# BiodataFeather_SymBioWare_001.net
KiCad netlist of a schematic drawn in EAGLE
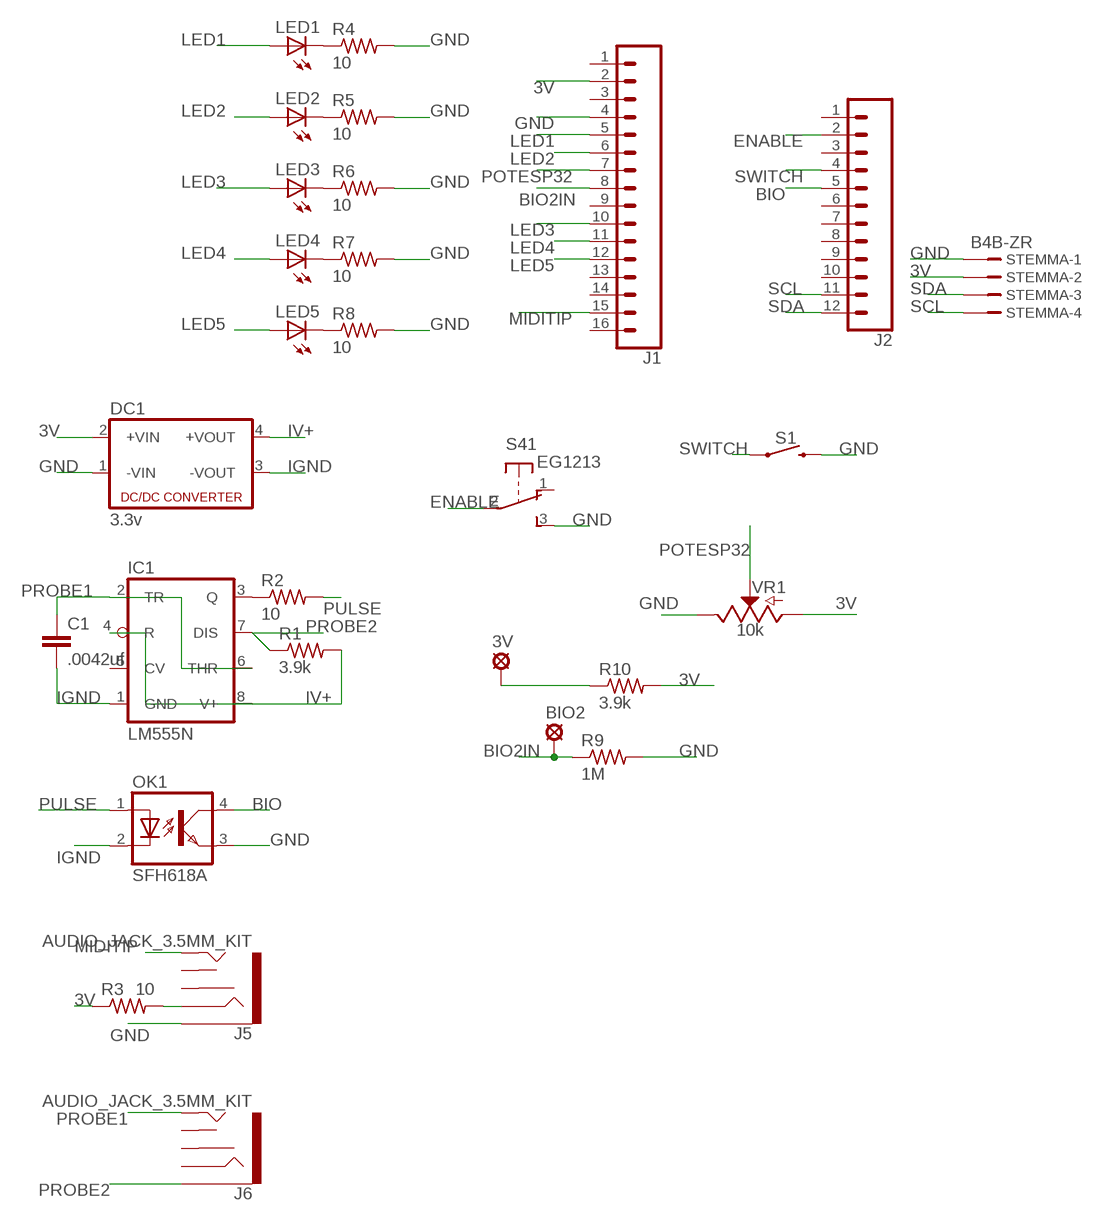
[diagram p0: schematic, sheet 1]

(export (version "E")
  (design (tool "Eeschema 10.0.6"))
  (components
    (comp (ref "3V")
      (value "SE14")
      (footprint "eagle-import:SE14")
      (libsource (lib "eagle-import") (part "SE14"))
    )
    (comp (ref "BIO2")
      (value "SE14")
      (footprint "eagle-import:SE14")
      (libsource (lib "eagle-import") (part "SE14"))
    )
    (comp (ref "C1")
      (value ".0042uf")
      (footprint "eagle-import:C2.5-2")
      (libsource (lib "eagle-import") (part "C2.5/2"))
    )
    (comp (ref "DC1")
      (value "3.3v")
      (footprint "eagle-import:NME")
      (fields (field (name "MF") "C & D TECHNOLOGIES, INC") (field (name "MPN") "NME1205D"))
      (libsource (lib "eagle-import") (part "NME"))
    )
    (comp (ref "IC1")
      (value "LM555N")
      (footprint "eagle-import:DIL08")
      (libsource (lib "eagle-import") (part "555NLM"))
    )
    (comp (ref "J1")
      (value "CONN_161X16_NO_SILK")
      (footprint "eagle-import:1X16_NO_SILK")
      (libsource (lib "eagle-import") (part "CONN_161X16_NO_SILK"))
    )
    (comp (ref "J2")
      (value "CONN_12NO_SILK")
      (footprint "eagle-import:1X12_NO_SILK")
      (libsource (lib "eagle-import") (part "CONN_12NO_SILK"))
    )
    (comp (ref "J5")
      (value "AUDIO_JACK_3.5MM_KIT")
      (footprint "eagle-import:AUDIO-JACK-KIT")
      (libsource (lib "eagle-import") (part "AUDIO_JACK_3.5MM_KIT"))
    )
    (comp (ref "J6")
      (value "AUDIO_JACK_3.5MM_KIT")
      (footprint "eagle-import:AUDIO-JACK-KIT")
      (libsource (lib "eagle-import") (part "AUDIO_JACK_3.5MM_KIT"))
    )
    (comp (ref "LED1")
      (value "LED5MM")
      (footprint "eagle-import:LED5MM")
      (libsource (lib "eagle-import") (part "LED5MM"))
    )
    (comp (ref "LED2")
      (value "LED5MM")
      (footprint "eagle-import:LED5MM")
      (libsource (lib "eagle-import") (part "LED5MM"))
    )
    (comp (ref "LED3")
      (value "LED5MM")
      (footprint "eagle-import:LED5MM")
      (libsource (lib "eagle-import") (part "LED5MM"))
    )
    (comp (ref "LED4")
      (value "LED5MM")
      (footprint "eagle-import:LED5MM")
      (libsource (lib "eagle-import") (part "LED5MM"))
    )
    (comp (ref "LED5")
      (value "LED5MM")
      (footprint "eagle-import:LED5MM")
      (libsource (lib "eagle-import") (part "LED5MM"))
    )
    (comp (ref "OK1")
      (value "SFH618A")
      (footprint "eagle-import:DIP4")
      (fields (field (name "MF") "VISHAY/TELEFUNKEN") (field (name "MPN") "SFH618A-5"))
      (libsource (lib "eagle-import") (part "SFH618?A-5"))
    )
    (comp (ref "R1")
      (value "3.9k")
      (footprint "eagle-import:0204V")
      (libsource (lib "eagle-import") (part "R-US_0204/2V"))
    )
    (comp (ref "R2")
      (value "10")
      (footprint "eagle-import:0204V")
      (libsource (lib "eagle-import") (part "R-US_0204/2V"))
    )
    (comp (ref "R3")
      (value "10")
      (footprint "eagle-import:0204V")
      (libsource (lib "eagle-import") (part "R-US_0204/2V"))
    )
    (comp (ref "R4")
      (value "10")
      (footprint "eagle-import:0204V")
      (libsource (lib "eagle-import") (part "R-US_0204/2V"))
    )
    (comp (ref "R5")
      (value "10")
      (footprint "eagle-import:0204V")
      (libsource (lib "eagle-import") (part "R-US_0204/2V"))
    )
    (comp (ref "R6")
      (value "10")
      (footprint "eagle-import:0204V")
      (libsource (lib "eagle-import") (part "R-US_0204/2V"))
    )
    (comp (ref "R7")
      (value "10")
      (footprint "eagle-import:0204V")
      (libsource (lib "eagle-import") (part "R-US_0204/2V"))
    )
    (comp (ref "R8")
      (value "10")
      (footprint "eagle-import:0204V")
      (libsource (lib "eagle-import") (part "R-US_0204/2V"))
    )
    (comp (ref "R9")
      (value "1M")
      (footprint "eagle-import:0204V")
      (libsource (lib "eagle-import") (part "R-US_0204/2V"))
    )
    (comp (ref "R10")
      (value "3.9k")
      (footprint "eagle-import:0204V")
      (libsource (lib "eagle-import") (part "R-US_0204/2V"))
    )
    (comp (ref "S1")
      (value "MOMENTARY-SWITCH-SPST-PTH-6.0MM")
      (footprint "eagle-import:TACTILE_SWITCH_PTH_6.0MM")
      (libsource (lib "eagle-import") (part "MOMENTARY-SWITCH-SPST-PTH-6.0MM"))
    )
    (comp (ref "S4")
      (value "EG1213")
      (footprint "eagle-import:EG1213")
      (libsource (lib "eagle-import") (part "EG1213"))
    )
    (comp (ref "STEMMA")
      (value "B4B-ZR")
      (footprint "eagle-import:B4B-ZR")
      (fields (field (name "MF") "FARNELL") (field (name "MPN") "B4B-ZR(LF)(SN)"))
      (libsource (lib "eagle-import") (part "?4B-ZRB"))
    )
    (comp (ref "VR1")
      (value "10k")
      (footprint "eagle-import:POT-PTH-ALPS-KIT")
      (libsource (lib "eagle-import") (part "POTENTIOMETER-PTH-9MM-1/20W-20%-KIT"))
    )
  )
  (nets
    (net (code "1") (name "/3V") (class "Default")
      (node (ref "DC1") (pin "2") (pinfunction "+VIN_2") (pintype "passive"))
      (node (ref "J1") (pin "2") (pinfunction "2_2") (pintype "passive"))
      (node (ref "R10") (pin "2") (pinfunction "2_2") (pintype "passive"))
      (node (ref "R3") (pin "1") (pinfunction "1_1") (pintype "passive"))
      (node (ref "STEMMA") (pin "2") (pinfunction "1_2") (pintype "passive"))
      (node (ref "VR1") (pin "P$3") (pinfunction "A_P$3") (pintype "passive"))
    )
    (net (code "2") (name "/BIO") (class "Default")
      (node (ref "J2") (pin "5") (pinfunction "5_5") (pintype "passive"))
      (node (ref "OK1") (pin "4") (pinfunction "COL_4") (pintype "passive"))
    )
    (net (code "3") (name "/BIO2IN") (class "Default")
      (node (ref "BIO2") (pin "MP") (pinfunction "MP_MP") (pintype "passive"))
      (node (ref "J1") (pin "8") (pinfunction "8_8") (pintype "passive"))
      (node (ref "R9") (pin "1") (pinfunction "1_1") (pintype "passive"))
    )
    (net (code "4") (name "/ENABLE") (class "Default")
      (node (ref "J2") (pin "2") (pinfunction "2_2") (pintype "passive"))
      (node (ref "S4") (pin "2") (pinfunction "P_2") (pintype "passive"))
    )
    (net (code "5") (name "/GND") (class "Default")
      (node (ref "DC1") (pin "1") (pinfunction "-VIN_1") (pintype "passive"))
      (node (ref "J1") (pin "4") (pinfunction "4_4") (pintype "passive"))
      (node (ref "J5") (pin "SLEEVE") (pinfunction "SLEEVE_SLEEVE") (pintype "bidirectional"))
      (node (ref "OK1") (pin "3") (pinfunction "EMIT_3") (pintype "passive"))
      (node (ref "R4") (pin "2") (pinfunction "2_2") (pintype "passive"))
      (node (ref "R5") (pin "2") (pinfunction "2_2") (pintype "passive"))
      (node (ref "R6") (pin "2") (pinfunction "2_2") (pintype "passive"))
      (node (ref "R7") (pin "2") (pinfunction "2_2") (pintype "passive"))
      (node (ref "R8") (pin "2") (pinfunction "2_2") (pintype "passive"))
      (node (ref "R9") (pin "2") (pinfunction "2_2") (pintype "passive"))
      (node (ref "S1") (pin "3") (pinfunction "2_3") (pintype "passive"))
      (node (ref "S4") (pin "3") (pinfunction "S_3") (pintype "passive"))
      (node (ref "STEMMA") (pin "1") (pinfunction "1_1") (pintype "passive"))
      (node (ref "VR1") (pin "P$1") (pinfunction "E_P$1") (pintype "passive"))
    )
    (net (code "6") (name "/IGND") (class "Default")
      (node (ref "C1") (pin "2") (pinfunction "2_2") (pintype "passive"))
      (node (ref "DC1") (pin "3") (pinfunction "-VOUT_3") (pintype "passive"))
      (node (ref "IC1") (pin "1") (pinfunction "GND_1") (pintype "power_in"))
      (node (ref "OK1") (pin "2") (pinfunction "C_2") (pintype "passive"))
    )
    (net (code "7") (name "/IV+") (class "Default")
      (node (ref "DC1") (pin "4") (pinfunction "+VOUT_4") (pintype "passive"))
      (node (ref "IC1") (pin "4") (pinfunction "R_4") (pintype "input"))
      (node (ref "IC1") (pin "8") (pinfunction "V+_8") (pintype "power_in"))
      (node (ref "R1") (pin "2") (pinfunction "2_2") (pintype "passive"))
    )
    (net (code "8") (name "/LED1") (class "Default")
      (node (ref "J1") (pin "5") (pinfunction "5_5") (pintype "passive"))
      (node (ref "LED1") (pin "A") (pinfunction "A_A") (pintype "passive"))
    )
    (net (code "9") (name "/LED2") (class "Default")
      (node (ref "J1") (pin "6") (pinfunction "6_6") (pintype "passive"))
      (node (ref "LED2") (pin "A") (pinfunction "A_A") (pintype "passive"))
    )
    (net (code "10") (name "/LED3") (class "Default")
      (node (ref "J1") (pin "10") (pinfunction "10_10") (pintype "passive"))
      (node (ref "LED3") (pin "A") (pinfunction "A_A") (pintype "passive"))
    )
    (net (code "11") (name "/LED4") (class "Default")
      (node (ref "J1") (pin "11") (pinfunction "11_11") (pintype "passive"))
      (node (ref "LED4") (pin "A") (pinfunction "A_A") (pintype "passive"))
    )
    (net (code "12") (name "/LED5") (class "Default")
      (node (ref "J1") (pin "12") (pinfunction "12_12") (pintype "passive"))
      (node (ref "LED5") (pin "A") (pinfunction "A_A") (pintype "passive"))
    )
    (net (code "13") (name "/MIDITIP") (class "Default")
      (node (ref "J1") (pin "15") (pinfunction "15_15") (pintype "passive"))
      (node (ref "J5") (pin "TIP") (pinfunction "TIP_TIP") (pintype "bidirectional"))
    )
    (net (code "14") (name "/POTESP32") (class "Default")
      (node (ref "J1") (pin "7") (pinfunction "7_7") (pintype "passive"))
      (node (ref "VR1") (pin "P$2") (pinfunction "S_P$2") (pintype "passive"))
    )
    (net (code "15") (name "/PROBE1") (class "Default")
      (node (ref "C1") (pin "1") (pinfunction "1_1") (pintype "passive"))
      (node (ref "IC1") (pin "2") (pinfunction "TR_2") (pintype "input"))
      (node (ref "IC1") (pin "6") (pinfunction "THR_6") (pintype "input"))
      (node (ref "J6") (pin "TIP") (pinfunction "TIP_TIP") (pintype "bidirectional"))
    )
    (net (code "16") (name "/PROBE2") (class "Default")
      (node (ref "IC1") (pin "7") (pinfunction "DIS_7") (pintype "input"))
      (node (ref "J6") (pin "SLEEVE") (pinfunction "SLEEVE_SLEEVE") (pintype "bidirectional"))
      (node (ref "R1") (pin "1") (pinfunction "1_1") (pintype "passive"))
    )
    (net (code "17") (name "/PULSE") (class "Default")
      (node (ref "OK1") (pin "1") (pinfunction "A_1") (pintype "passive"))
      (node (ref "R2") (pin "2") (pinfunction "2_2") (pintype "passive"))
    )
    (net (code "18") (name "/SCL") (class "Default")
      (node (ref "J2") (pin "11") (pinfunction "11_11") (pintype "passive"))
      (node (ref "STEMMA") (pin "4") (pinfunction "1_4") (pintype "passive"))
    )
    (net (code "19") (name "/SDA") (class "Default")
      (node (ref "J2") (pin "12") (pinfunction "12_12") (pintype "passive"))
      (node (ref "STEMMA") (pin "3") (pinfunction "1_3") (pintype "passive"))
    )
    (net (code "20") (name "/SWITCH") (class "Default")
      (node (ref "J2") (pin "4") (pinfunction "4_4") (pintype "passive"))
      (node (ref "S1") (pin "1") (pinfunction "1_1") (pintype "passive"))
    )
    (net (code "21") (name "Net-(3V-PadMP)") (class "Default")
      (node (ref "3V") (pin "MP") (pinfunction "MP_MP") (pintype "passive"))
      (node (ref "R10") (pin "1") (pinfunction "1_1") (pintype "passive"))
    )
    (net (code "22") (name "Net-(IC1-Q)") (class "Default")
      (node (ref "IC1") (pin "3") (pinfunction "Q_3") (pintype "output"))
      (node (ref "R2") (pin "1") (pinfunction "1_1") (pintype "passive"))
    )
    (net (code "23") (name "Net-(J5-PadRING)") (class "Default")
      (node (ref "J5") (pin "RING") (pinfunction "RING_RING") (pintype "bidirectional"))
      (node (ref "R3") (pin "2") (pinfunction "2_2") (pintype "passive"))
    )
    (net (code "24") (name "Net-(LED1-C)") (class "Default")
      (node (ref "LED1") (pin "K") (pinfunction "C_K") (pintype "passive"))
      (node (ref "R4") (pin "1") (pinfunction "1_1") (pintype "passive"))
    )
    (net (code "25") (name "Net-(LED2-C)") (class "Default")
      (node (ref "LED2") (pin "K") (pinfunction "C_K") (pintype "passive"))
      (node (ref "R5") (pin "1") (pinfunction "1_1") (pintype "passive"))
    )
    (net (code "26") (name "Net-(LED3-C)") (class "Default")
      (node (ref "LED3") (pin "K") (pinfunction "C_K") (pintype "passive"))
      (node (ref "R6") (pin "1") (pinfunction "1_1") (pintype "passive"))
    )
    (net (code "27") (name "Net-(LED4-C)") (class "Default")
      (node (ref "LED4") (pin "K") (pinfunction "C_K") (pintype "passive"))
      (node (ref "R7") (pin "1") (pinfunction "1_1") (pintype "passive"))
    )
    (net (code "28") (name "Net-(LED5-C)") (class "Default")
      (node (ref "LED5") (pin "K") (pinfunction "C_K") (pintype "passive"))
      (node (ref "R8") (pin "1") (pinfunction "1_1") (pintype "passive"))
    )
    (net (code "29") (name "unconnected-(IC1-CV-Pad5)") (class "Default")
      (node (ref "IC1") (pin "5") (pinfunction "CV_5") (pintype "input"))
    )
    (net (code "30") (name "unconnected-(J1-Pad1)") (class "Default")
      (node (ref "J1") (pin "1") (pinfunction "1_1") (pintype "passive"))
    )
    (net (code "31") (name "unconnected-(J1-Pad3)") (class "Default")
      (node (ref "J1") (pin "3") (pinfunction "3_3") (pintype "passive"))
    )
    (net (code "32") (name "unconnected-(J1-Pad9)") (class "Default")
      (node (ref "J1") (pin "9") (pinfunction "9_9") (pintype "passive"))
    )
    (net (code "33") (name "unconnected-(J1-Pad13)") (class "Default")
      (node (ref "J1") (pin "13") (pinfunction "13_13") (pintype "passive"))
    )
    (net (code "34") (name "unconnected-(J1-Pad14)") (class "Default")
      (node (ref "J1") (pin "14") (pinfunction "14_14") (pintype "passive"))
    )
    (net (code "35") (name "unconnected-(J1-Pad16)") (class "Default")
      (node (ref "J1") (pin "16") (pinfunction "16_16") (pintype "passive"))
    )
    (net (code "36") (name "unconnected-(J2-Pad1)") (class "Default")
      (node (ref "J2") (pin "1") (pinfunction "1_1") (pintype "passive"))
    )
    (net (code "37") (name "unconnected-(J2-Pad3)") (class "Default")
      (node (ref "J2") (pin "3") (pinfunction "3_3") (pintype "passive"))
    )
    (net (code "38") (name "unconnected-(J2-Pad6)") (class "Default")
      (node (ref "J2") (pin "6") (pinfunction "6_6") (pintype "passive"))
    )
    (net (code "39") (name "unconnected-(J2-Pad7)") (class "Default")
      (node (ref "J2") (pin "7") (pinfunction "7_7") (pintype "passive"))
    )
    (net (code "40") (name "unconnected-(J2-Pad8)") (class "Default")
      (node (ref "J2") (pin "8") (pinfunction "8_8") (pintype "passive"))
    )
    (net (code "41") (name "unconnected-(J2-Pad9)") (class "Default")
      (node (ref "J2") (pin "9") (pinfunction "9_9") (pintype "passive"))
    )
    (net (code "42") (name "unconnected-(J2-Pad10)") (class "Default")
      (node (ref "J2") (pin "10") (pinfunction "10_10") (pintype "passive"))
    )
    (net (code "43") (name "unconnected-(J5-PadRSH)") (class "Default")
      (node (ref "J5") (pin "RSH") (pinfunction "RSH_RSH") (pintype "bidirectional"))
    )
    (net (code "44") (name "unconnected-(J5-PadTSH)") (class "Default")
      (node (ref "J5") (pin "TSH") (pinfunction "TSH_TSH") (pintype "bidirectional"))
    )
    (net (code "45") (name "unconnected-(J6-PadRING)") (class "Default")
      (node (ref "J6") (pin "RING") (pinfunction "RING_RING") (pintype "bidirectional"))
    )
    (net (code "46") (name "unconnected-(J6-PadRSH)") (class "Default")
      (node (ref "J6") (pin "RSH") (pinfunction "RSH_RSH") (pintype "bidirectional"))
    )
    (net (code "47") (name "unconnected-(J6-PadTSH)") (class "Default")
      (node (ref "J6") (pin "TSH") (pinfunction "TSH_TSH") (pintype "bidirectional"))
    )
    (net (code "48") (name "unconnected-(S4A-O-Pad1)") (class "Default")
      (node (ref "S4") (pin "1") (pinfunction "O_1") (pintype "passive"))
    )
  )
)
